# UART-to-ESP32-WROOM.net
KiCad netlist of a schematic drawn in EAGLE
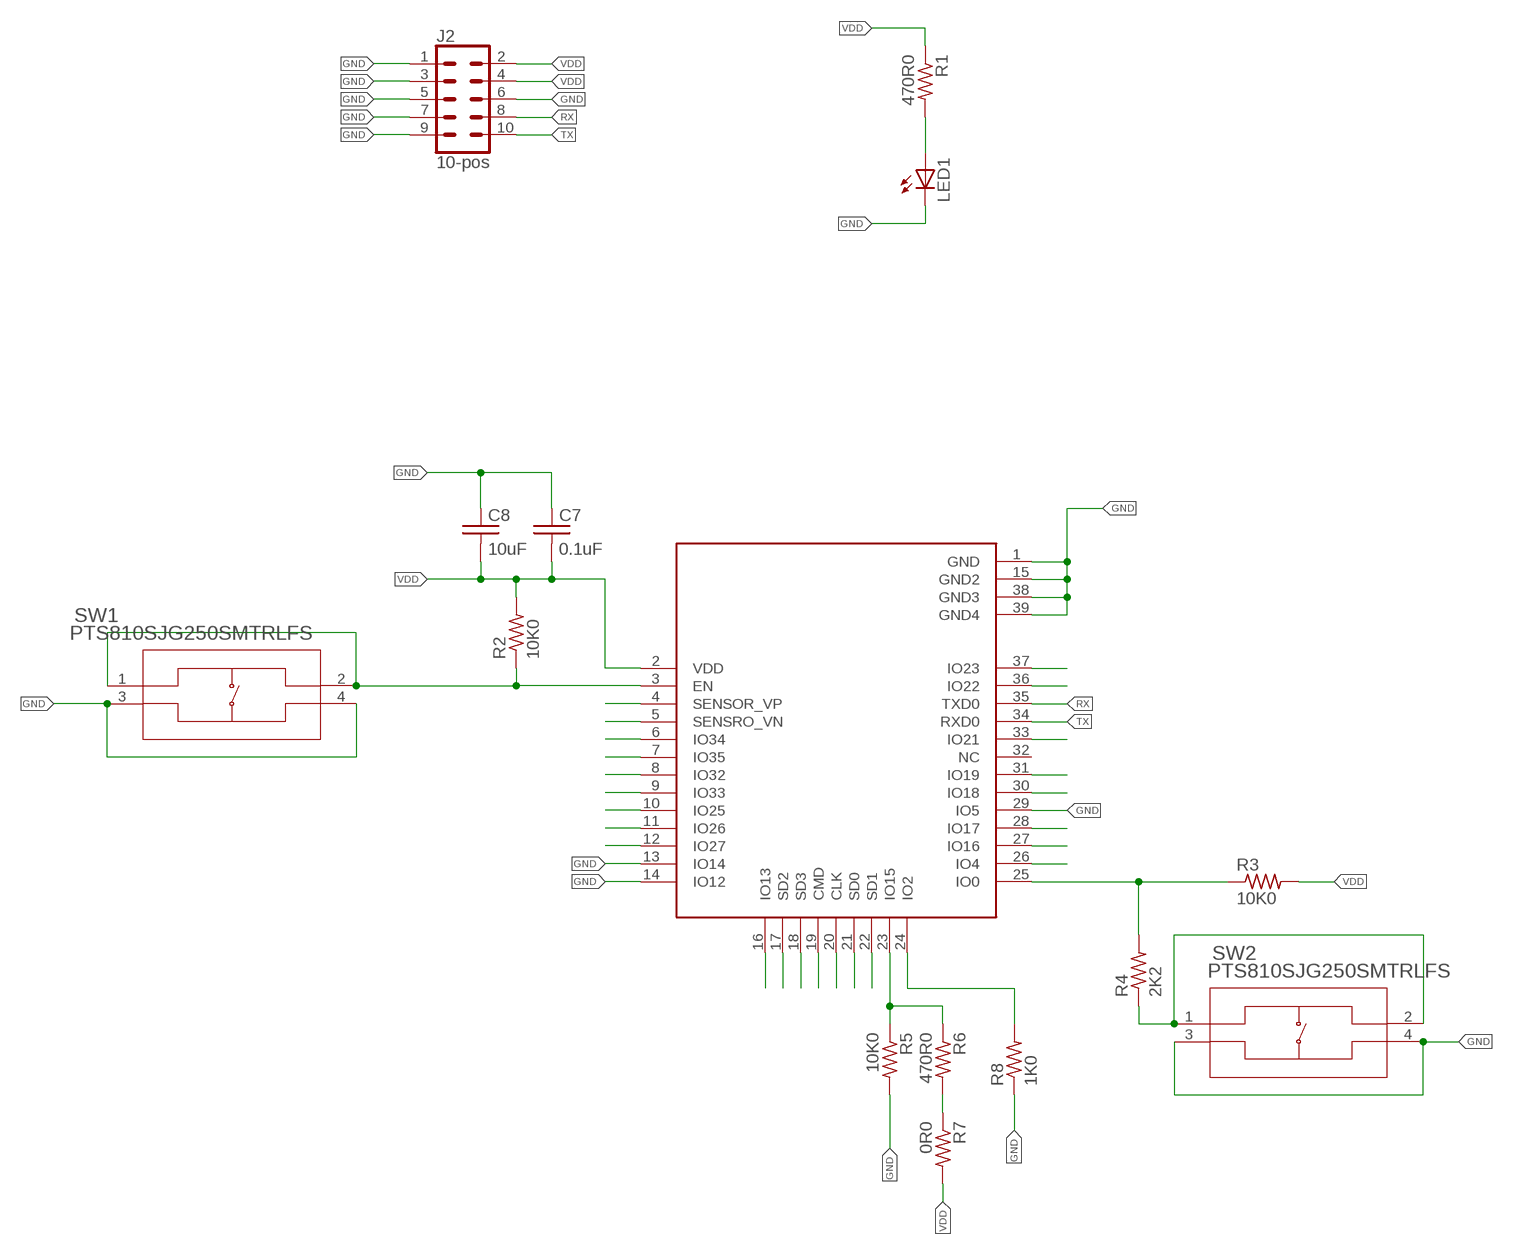
[diagram p0: schematic, sheet 1]

(export (version "E")
  (design (tool "Eeschema 10.0.6"))
  (components
    (comp (ref "C7")
      (value "0.1uF")
      (footprint "eagle-import:0402")
      (fields (field (name "PARTNO") "CL05F104ZO5NNNC"))
      (libsource (lib "eagle-import") (part "C_0402_0.1UF"))
    )
    (comp (ref "C8")
      (value "10uF")
      (footprint "eagle-import:0402")
      (fields (field (name "PARTNO") "CL05A106MP8NUB8"))
      (libsource (lib "eagle-import") (part "C_0402_10UF"))
    )
    (comp (ref "J2")
      (value "10-pos")
      (footprint "eagle-import:2X5")
      (fields (field (name "PARTNO") "PH2RA-10-UA"))
      (libsource (lib "eagle-import") (part "CONN_05X2_RAPTH"))
    )
    (comp (ref "LED1")
      (value "Green")
      (footprint "eagle-import:LED_0805_GREEN")
      (fields (field (name "PARTNO") "LG R971-KN-1"))
      (libsource (lib "eagle-import") (part "LED_0805_GREEN"))
    )
    (comp (ref "R1")
      (value "470R0")
      (footprint "eagle-import:0402")
      (fields (field (name "PARTNO") "RMCF0402JT470R"))
      (libsource (lib "eagle-import") (part "R_0402_470R0"))
    )
    (comp (ref "R2")
      (value "10K0")
      (footprint "eagle-import:0402")
      (fields (field (name "PARTNO") "RMCF0402JT10K0"))
      (libsource (lib "eagle-import") (part "R_0402_10K0"))
    )
    (comp (ref "R3")
      (value "10K0")
      (footprint "eagle-import:0402")
      (fields (field (name "PARTNO") "RMCF0402JT10K0"))
      (libsource (lib "eagle-import") (part "R_0402_10K0"))
    )
    (comp (ref "R4")
      (value "2K2")
      (footprint "eagle-import:0402")
      (fields (field (name "PARTNO") "RMCF0402JT2K20"))
      (libsource (lib "eagle-import") (part "R_0402_2K2"))
    )
    (comp (ref "R5")
      (value "10K0")
      (footprint "eagle-import:0402")
      (fields (field (name "PARTNO") "RMCF0402JT10K0"))
      (libsource (lib "eagle-import") (part "R_0402_10K0"))
    )
    (comp (ref "R6")
      (value "470R0")
      (footprint "eagle-import:0402")
      (fields (field (name "PARTNO") "RMCF0402JT470R"))
      (libsource (lib "eagle-import") (part "R_0402_470R0"))
    )
    (comp (ref "R7")
      (value "0R0")
      (footprint "eagle-import:0402")
      (libsource (lib "eagle-import") (part "R_0402"))
    )
    (comp (ref "R8")
      (value "1K0")
      (footprint "eagle-import:0402")
      (fields (field (name "PARTNO") "CRG0402J1K0"))
      (libsource (lib "eagle-import") (part "R_0402_1K0"))
    )
    (comp (ref "SW1")
      (value "PTS810SJG250SMTRLFS")
      (footprint "eagle-import:PTS810")
      (fields (field (name "COPYRIGHT") "Copyright (C) 2018 Accelerated Designs. All rights reserved"))
      (libsource (lib "eagle-import") (part "PTS810SJG250SMTRLFS"))
    )
    (comp (ref "SW2")
      (value "PTS810SJG250SMTRLFS")
      (footprint "eagle-import:PTS810")
      (fields (field (name "COPYRIGHT") "Copyright (C) 2018 Accelerated Designs. All rights reserved"))
      (libsource (lib "eagle-import") (part "PTS810SJG250SMTRLFS"))
    )
    (comp (ref "U2")
      (value "ESP32-WROOM-32D")
      (footprint "eagle-import:ESP32-WROOM-32D")
      (libsource (lib "eagle-import") (part "ESP32-WROOM-32D"))
    )
  )
  (nets
    (net (code "1") (name "GND") (class "Default")
      (node (ref "C7") (pin "P$1") (pinfunction "1_P$1") (pintype "passive"))
      (node (ref "C8") (pin "P$1") (pinfunction "1_P$1") (pintype "passive"))
      (node (ref "J2") (pin "1") (pinfunction "1_1") (pintype "passive"))
      (node (ref "J2") (pin "3") (pinfunction "3_3") (pintype "passive"))
      (node (ref "J2") (pin "5") (pinfunction "5_5") (pintype "passive"))
      (node (ref "J2") (pin "6") (pinfunction "6_6") (pintype "passive"))
      (node (ref "J2") (pin "7") (pinfunction "7_7") (pintype "passive"))
      (node (ref "J2") (pin "9") (pinfunction "9_9") (pintype "passive"))
      (node (ref "LED1") (pin "C") (pinfunction "C_C") (pintype "passive"))
      (node (ref "R5") (pin "P$2") (pinfunction "2_P$2") (pintype "passive"))
      (node (ref "R8") (pin "P$1") (pinfunction "1_P$1") (pintype "passive"))
      (node (ref "SW1") (pin "3") (pinfunction "3_3") (pintype "passive"))
      (node (ref "SW1") (pin "4") (pinfunction "4_4") (pintype "passive"))
      (node (ref "SW2") (pin "3") (pinfunction "3_3") (pintype "passive"))
      (node (ref "SW2") (pin "4") (pinfunction "4_4") (pintype "passive"))
      (node (ref "U2") (pin "1") (pinfunction "GND_1") (pintype "bidirectional"))
      (node (ref "U2") (pin "13") (pinfunction "IO14_13") (pintype "bidirectional"))
      (node (ref "U2") (pin "14") (pinfunction "IO12_14") (pintype "bidirectional"))
      (node (ref "U2") (pin "15") (pinfunction "GND2_15") (pintype "bidirectional"))
      (node (ref "U2") (pin "29") (pinfunction "IO5_29") (pintype "bidirectional"))
      (node (ref "U2") (pin "38") (pinfunction "GND3_38") (pintype "bidirectional"))
      (node (ref "U2") (pin "39") (pinfunction "GND4_39") (pintype "bidirectional"))
    )
    (net (code "2") (name "Net-(R1-2)") (class "Default")
      (node (ref "LED1") (pin "A") (pinfunction "A_A") (pintype "passive"))
      (node (ref "R1") (pin "P$2") (pinfunction "2_P$2") (pintype "passive"))
    )
    (net (code "3") (name "Net-(R2-1)") (class "Default")
      (node (ref "R2") (pin "P$1") (pinfunction "1_P$1") (pintype "passive"))
      (node (ref "SW1") (pin "1") (pinfunction "1_1") (pintype "passive"))
      (node (ref "SW1") (pin "2") (pinfunction "2_2") (pintype "passive"))
      (node (ref "U2") (pin "3") (pinfunction "EN_3") (pintype "bidirectional"))
    )
    (net (code "4") (name "Net-(R3-1)") (class "Default")
      (node (ref "R3") (pin "P$1") (pinfunction "1_P$1") (pintype "passive"))
      (node (ref "R4") (pin "P$2") (pinfunction "2_P$2") (pintype "passive"))
      (node (ref "U2") (pin "25") (pinfunction "IO0_25") (pintype "bidirectional"))
    )
    (net (code "5") (name "Net-(R4-1)") (class "Default")
      (node (ref "R4") (pin "P$1") (pinfunction "1_P$1") (pintype "passive"))
      (node (ref "SW2") (pin "1") (pinfunction "1_1") (pintype "passive"))
      (node (ref "SW2") (pin "2") (pinfunction "2_2") (pintype "passive"))
    )
    (net (code "6") (name "Net-(R5-1)") (class "Default")
      (node (ref "R5") (pin "P$1") (pinfunction "1_P$1") (pintype "passive"))
      (node (ref "R6") (pin "P$1") (pinfunction "1_P$1") (pintype "passive"))
      (node (ref "U2") (pin "23") (pinfunction "IO15_23") (pintype "bidirectional"))
    )
    (net (code "7") (name "Net-(R6-2)") (class "Default")
      (node (ref "R6") (pin "P$2") (pinfunction "2_P$2") (pintype "passive"))
      (node (ref "R7") (pin "P$1") (pinfunction "1_P$1") (pintype "passive"))
    )
    (net (code "8") (name "Net-(R8-2)") (class "Default")
      (node (ref "R8") (pin "P$2") (pinfunction "2_P$2") (pintype "passive"))
      (node (ref "U2") (pin "24") (pinfunction "IO2_24") (pintype "bidirectional"))
    )
    (net (code "9") (name "RX") (class "Default")
      (node (ref "J2") (pin "8") (pinfunction "8_8") (pintype "passive"))
      (node (ref "U2") (pin "35") (pinfunction "TXD0_35") (pintype "bidirectional"))
    )
    (net (code "10") (name "TX") (class "Default")
      (node (ref "J2") (pin "10") (pinfunction "10_10") (pintype "passive"))
      (node (ref "U2") (pin "34") (pinfunction "RXD0_34") (pintype "bidirectional"))
    )
    (net (code "11") (name "VDD") (class "Default")
      (node (ref "C7") (pin "P$2") (pinfunction "2_P$2") (pintype "passive"))
      (node (ref "C8") (pin "P$2") (pinfunction "2_P$2") (pintype "passive"))
      (node (ref "J2") (pin "2") (pinfunction "2_2") (pintype "passive"))
      (node (ref "J2") (pin "4") (pinfunction "4_4") (pintype "passive"))
      (node (ref "R1") (pin "P$1") (pinfunction "1_P$1") (pintype "passive"))
      (node (ref "R2") (pin "P$2") (pinfunction "2_P$2") (pintype "passive"))
      (node (ref "R3") (pin "P$2") (pinfunction "2_P$2") (pintype "passive"))
      (node (ref "R7") (pin "P$2") (pinfunction "2_P$2") (pintype "passive"))
      (node (ref "U2") (pin "2") (pinfunction "VDD_2") (pintype "bidirectional"))
    )
    (net (code "12") (name "unconnected-(U2-CLK-Pad20)") (class "Default")
      (node (ref "U2") (pin "20") (pinfunction "CLK_20") (pintype "bidirectional"))
    )
    (net (code "13") (name "unconnected-(U2-CMD-Pad19)") (class "Default")
      (node (ref "U2") (pin "19") (pinfunction "CMD_19") (pintype "bidirectional"))
    )
    (net (code "14") (name "unconnected-(U2-IO4-Pad26)") (class "Default")
      (node (ref "U2") (pin "26") (pinfunction "IO4_26") (pintype "bidirectional"))
    )
    (net (code "15") (name "unconnected-(U2-IO13-Pad16)") (class "Default")
      (node (ref "U2") (pin "16") (pinfunction "IO13_16") (pintype "bidirectional"))
    )
    (net (code "16") (name "unconnected-(U2-IO16-Pad27)") (class "Default")
      (node (ref "U2") (pin "27") (pinfunction "IO16_27") (pintype "bidirectional"))
    )
    (net (code "17") (name "unconnected-(U2-IO17-Pad28)") (class "Default")
      (node (ref "U2") (pin "28") (pinfunction "IO17_28") (pintype "bidirectional"))
    )
    (net (code "18") (name "unconnected-(U2-IO18-Pad30)") (class "Default")
      (node (ref "U2") (pin "30") (pinfunction "IO18_30") (pintype "bidirectional"))
    )
    (net (code "19") (name "unconnected-(U2-IO19-Pad31)") (class "Default")
      (node (ref "U2") (pin "31") (pinfunction "IO19_31") (pintype "bidirectional"))
    )
    (net (code "20") (name "unconnected-(U2-IO21-Pad33)") (class "Default")
      (node (ref "U2") (pin "33") (pinfunction "IO21_33") (pintype "bidirectional"))
    )
    (net (code "21") (name "unconnected-(U2-IO22-Pad36)") (class "Default")
      (node (ref "U2") (pin "36") (pinfunction "IO22_36") (pintype "bidirectional"))
    )
    (net (code "22") (name "unconnected-(U2-IO23-Pad37)") (class "Default")
      (node (ref "U2") (pin "37") (pinfunction "IO23_37") (pintype "bidirectional"))
    )
    (net (code "23") (name "unconnected-(U2-IO25-Pad10)") (class "Default")
      (node (ref "U2") (pin "10") (pinfunction "IO25_10") (pintype "bidirectional"))
    )
    (net (code "24") (name "unconnected-(U2-IO26-Pad11)") (class "Default")
      (node (ref "U2") (pin "11") (pinfunction "IO26_11") (pintype "bidirectional"))
    )
    (net (code "25") (name "unconnected-(U2-IO27-Pad12)") (class "Default")
      (node (ref "U2") (pin "12") (pinfunction "IO27_12") (pintype "bidirectional"))
    )
    (net (code "26") (name "unconnected-(U2-IO32-Pad8)") (class "Default")
      (node (ref "U2") (pin "8") (pinfunction "IO32_8") (pintype "bidirectional"))
    )
    (net (code "27") (name "unconnected-(U2-IO33-Pad9)") (class "Default")
      (node (ref "U2") (pin "9") (pinfunction "IO33_9") (pintype "bidirectional"))
    )
    (net (code "28") (name "unconnected-(U2-IO34-Pad6)") (class "Default")
      (node (ref "U2") (pin "6") (pinfunction "IO34_6") (pintype "bidirectional"))
    )
    (net (code "29") (name "unconnected-(U2-IO35-Pad7)") (class "Default")
      (node (ref "U2") (pin "7") (pinfunction "IO35_7") (pintype "bidirectional"))
    )
    (net (code "30") (name "unconnected-(U2-NC-Pad32)") (class "Default")
      (node (ref "U2") (pin "32") (pinfunction "NC_32") (pintype "bidirectional"))
    )
    (net (code "31") (name "unconnected-(U2-SD0-Pad21)") (class "Default")
      (node (ref "U2") (pin "21") (pinfunction "SD0_21") (pintype "bidirectional"))
    )
    (net (code "32") (name "unconnected-(U2-SD1-Pad22)") (class "Default")
      (node (ref "U2") (pin "22") (pinfunction "SD1_22") (pintype "bidirectional"))
    )
    (net (code "33") (name "unconnected-(U2-SD2-Pad17)") (class "Default")
      (node (ref "U2") (pin "17") (pinfunction "SD2_17") (pintype "bidirectional"))
    )
    (net (code "34") (name "unconnected-(U2-SD3-Pad18)") (class "Default")
      (node (ref "U2") (pin "18") (pinfunction "SD3_18") (pintype "bidirectional"))
    )
    (net (code "35") (name "unconnected-(U2-SENSOR_VP-Pad4)") (class "Default")
      (node (ref "U2") (pin "4") (pinfunction "SENSOR_VP_4") (pintype "bidirectional"))
    )
    (net (code "36") (name "unconnected-(U2-SENSRO_VN-Pad5)") (class "Default")
      (node (ref "U2") (pin "5") (pinfunction "SENSRO_VN_5") (pintype "bidirectional"))
    )
  )
)
